# The_Flying_Jalapeno_v01.net
KiCad netlist of a schematic drawn in EAGLE
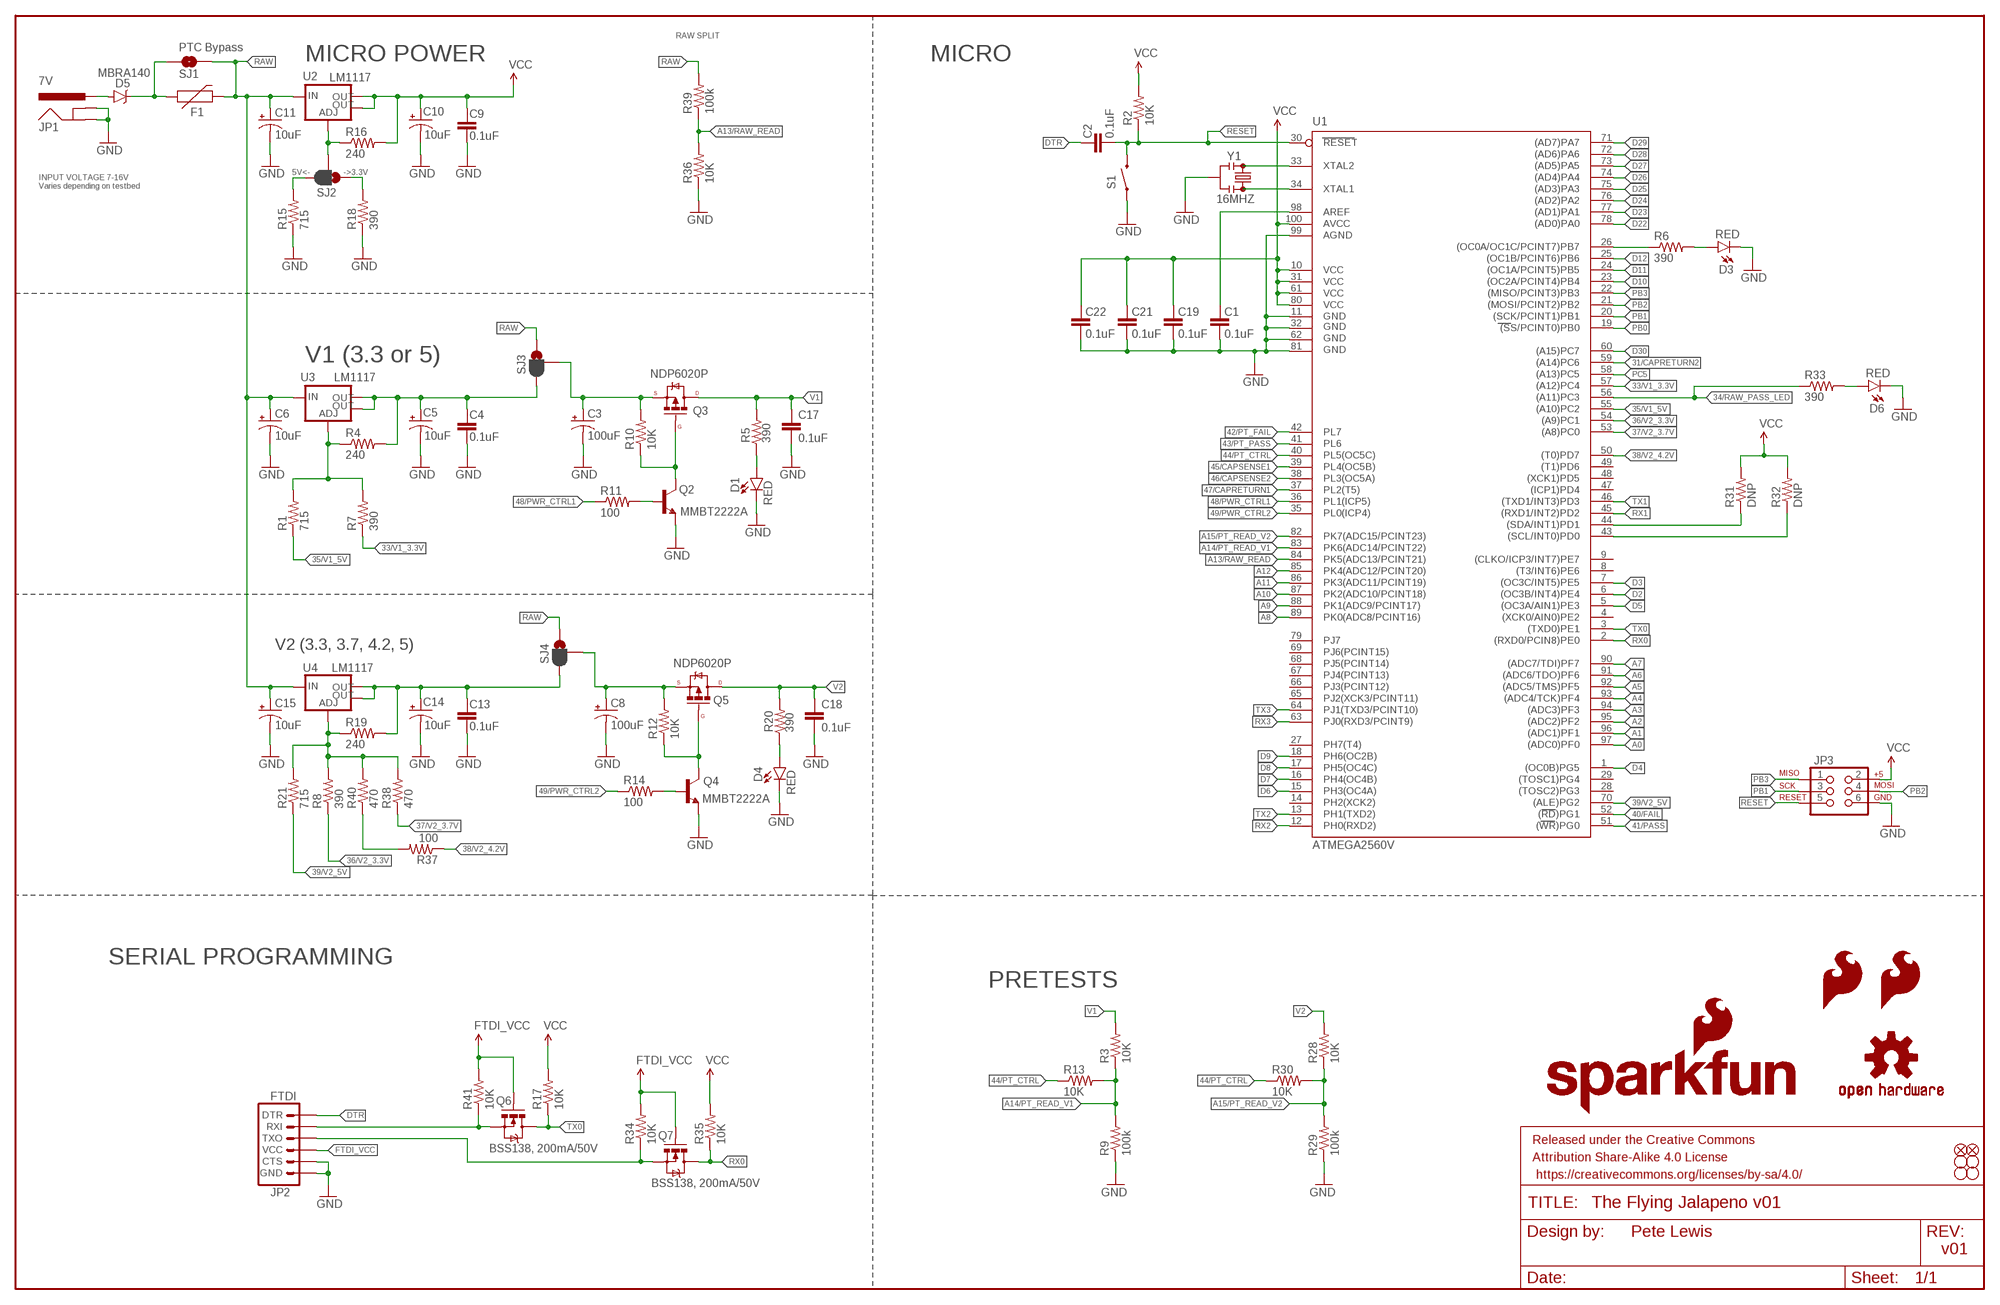
[diagram p0: schematic, sheet 1, part 1 of 2]
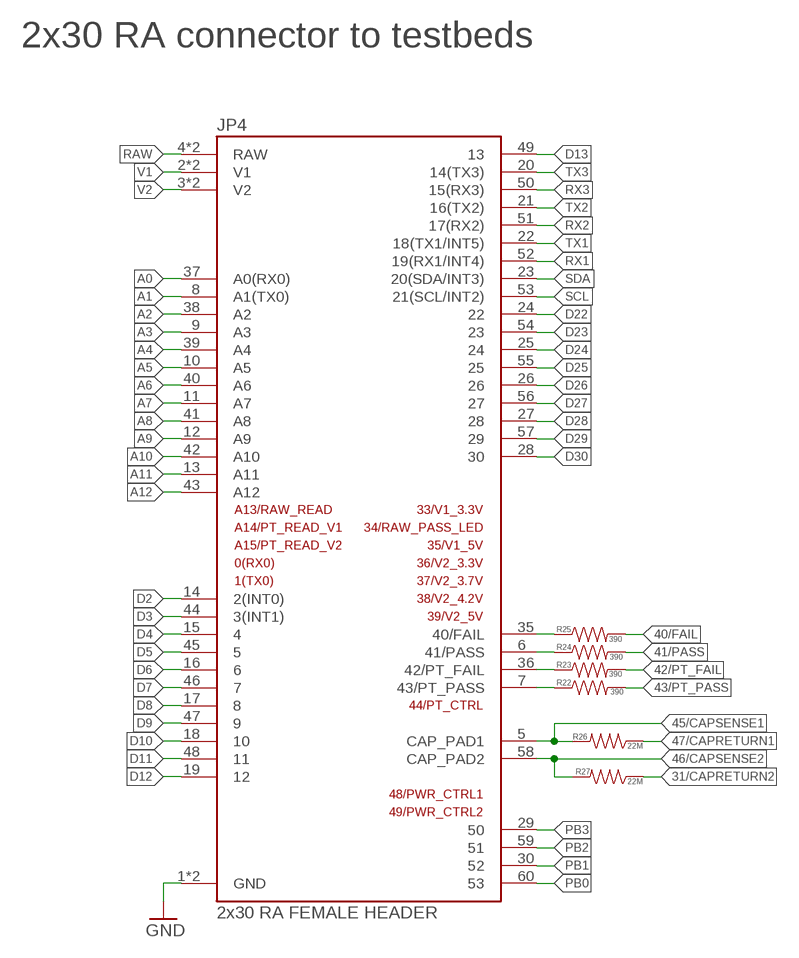
[diagram p1: schematic, sheet 1, part 2 of 2]

(export (version "E")
  (design (tool "Eeschema 10.0.6"))
  (components
    (comp (ref "C1")
      (value "0.1uF")
      (footprint "eagle-import:0603-CAP")
      (libsource (lib "eagle-import") (part "0.1UF-25V(+80/-20%)(0603)"))
    )
    (comp (ref "C2")
      (value "0.1uF")
      (footprint "eagle-import:0603-CAP")
      (libsource (lib "eagle-import") (part "0.1UF-25V(+80/-20%)(0603)"))
    )
    (comp (ref "C3")
      (value "100uF")
      (footprint "eagle-import:NIC_10X10.5_CAP")
      (libsource (lib "eagle-import") (part "100UF-63V-20%(ELECT)"))
    )
    (comp (ref "C4")
      (value "0.1uF")
      (footprint "eagle-import:0603-CAP")
      (libsource (lib "eagle-import") (part "0.1UF-25V(+80/-20%)(0603)"))
    )
    (comp (ref "C5")
      (value "10uF")
      (footprint "eagle-import:EIA3216")
      (libsource (lib "eagle-import") (part "10UF-16V-10%(TANT)"))
    )
    (comp (ref "C6")
      (value "10uF")
      (footprint "eagle-import:EIA3216")
      (libsource (lib "eagle-import") (part "10UF-16V-10%(TANT)"))
    )
    (comp (ref "C8")
      (value "100uF")
      (footprint "eagle-import:NIC_10X10.5_CAP")
      (libsource (lib "eagle-import") (part "100UF-63V-20%(ELECT)"))
    )
    (comp (ref "C9")
      (value "0.1uF")
      (footprint "eagle-import:0603-CAP")
      (libsource (lib "eagle-import") (part "0.1UF-25V(+80/-20%)(0603)"))
    )
    (comp (ref "C10")
      (value "10uF")
      (footprint "eagle-import:EIA3216")
      (libsource (lib "eagle-import") (part "10UF-16V-10%(TANT)"))
    )
    (comp (ref "C11")
      (value "10uF")
      (footprint "eagle-import:EIA3216")
      (libsource (lib "eagle-import") (part "10UF-16V-10%(TANT)"))
    )
    (comp (ref "C13")
      (value "0.1uF")
      (footprint "eagle-import:0603-CAP")
      (libsource (lib "eagle-import") (part "0.1UF-25V(+80/-20%)(0603)"))
    )
    (comp (ref "C14")
      (value "10uF")
      (footprint "eagle-import:EIA3216")
      (libsource (lib "eagle-import") (part "10UF-16V-10%(TANT)"))
    )
    (comp (ref "C15")
      (value "10uF")
      (footprint "eagle-import:EIA3216")
      (libsource (lib "eagle-import") (part "10UF-16V-10%(TANT)"))
    )
    (comp (ref "C17")
      (value "0.1uF")
      (footprint "eagle-import:0603-CAP")
      (libsource (lib "eagle-import") (part "0.1UF-25V(+80/-20%)(0603)"))
    )
    (comp (ref "C18")
      (value "0.1uF")
      (footprint "eagle-import:0603-CAP")
      (libsource (lib "eagle-import") (part "0.1UF-25V(+80/-20%)(0603)"))
    )
    (comp (ref "C19")
      (value "0.1uF")
      (footprint "eagle-import:0603-CAP")
      (libsource (lib "eagle-import") (part "0.1UF-25V(+80/-20%)(0603)"))
    )
    (comp (ref "C21")
      (value "0.1uF")
      (footprint "eagle-import:0603-CAP")
      (libsource (lib "eagle-import") (part "0.1UF-25V(+80/-20%)(0603)"))
    )
    (comp (ref "C22")
      (value "0.1uF")
      (footprint "eagle-import:0603-CAP")
      (libsource (lib "eagle-import") (part "0.1UF-25V(+80/-20%)(0603)"))
    )
    (comp (ref "D1")
      (value "RED")
      (footprint "eagle-import:LED-1206")
      (libsource (lib "eagle-import") (part "LED-RED1206"))
    )
    (comp (ref "D3")
      (value "RED")
      (footprint "eagle-import:LED-1206")
      (libsource (lib "eagle-import") (part "LED-RED1206"))
    )
    (comp (ref "D4")
      (value "RED")
      (footprint "eagle-import:LED-1206")
      (libsource (lib "eagle-import") (part "LED-RED1206"))
    )
    (comp (ref "D5")
      (value "MBRA140")
      (footprint "eagle-import:SMA-DIODE")
      (libsource (lib "eagle-import") (part "DIODE-SCHOTTKY-MBRA140"))
    )
    (comp (ref "D6")
      (value "RED")
      (footprint "eagle-import:LED-1206")
      (libsource (lib "eagle-import") (part "LED-RED1206"))
    )
    (comp (ref "F1")
      (value "PTCTHERMISTOR1206")
      (footprint "eagle-import:PTC-1206")
      (libsource (lib "eagle-import") (part "PTCTHERMISTOR1206"))
    )
    (comp (ref "FRAME1")
      (value "FRAME-LEDGER")
      (footprint "eagle-import:CREATIVE_COMMONS")
      (libsource (lib "eagle-import") (part "FRAME-LEDGER"))
    )
    (comp (ref "JP1")
      (value "7V")
      (footprint "eagle-import:POWER_JACK_PTH_LOCK")
      (libsource (lib "eagle-import") (part "POWER_JACKPTH_LOCK"))
    )
    (comp (ref "JP2")
      (value "FTDI")
      (footprint "eagle-import:1X06-SMD")
      (libsource (lib "eagle-import") (part "ARDUINO_SERIAL_PROGRAMSMD"))
    )
    (comp (ref "JP3")
      (value "AVR_SPI_PRG_6PTH")
      (footprint "eagle-import:2X3")
      (libsource (lib "eagle-import") (part "AVR_SPI_PRG_6PTH"))
    )
    (comp (ref "JP4")
      (value "2x30 RA FEMALE HEADER")
      (footprint "eagle-import:FLYING_JALAPENO_V2_F")
      (libsource (lib "eagle-import") (part "FLYING_JALAPENO_V2FEMALE"))
    )
    (comp (ref "JP5")
      (value "FIDUCIALUFIDUCIAL")
      (footprint "eagle-import:MICRO-FIDUCIAL")
      (libsource (lib "eagle-import") (part "FIDUCIALUFIDUCIAL"))
    )
    (comp (ref "JP8")
      (value "FIDUCIALUFIDUCIAL")
      (footprint "eagle-import:MICRO-FIDUCIAL")
      (libsource (lib "eagle-import") (part "FIDUCIALUFIDUCIAL"))
    )
    (comp (ref "LOGO1")
      (value "SFE_LOGO_NAME_FLAME.5_INCH")
      (footprint "eagle-import:SFE_LOGO_NAME_FLAME_.5")
      (libsource (lib "eagle-import") (part "SFE_LOGO_NAME_FLAME.5_INCH"))
    )
    (comp (ref "LOGO2")
      (value "SFE_LOGO_FLAME.3_INCH")
      (footprint "eagle-import:SFE_LOGO_FLAME_.3")
      (libsource (lib "eagle-import") (part "SFE_LOGO_FLAME.3_INCH"))
    )
    (comp (ref "LOGO3")
      (value "SFE_LOGO_FLAME.1_INCH")
      (footprint "eagle-import:SFE_LOGO_FLAME_.1")
      (libsource (lib "eagle-import") (part "SFE_LOGO_FLAME.1_INCH"))
    )
    (comp (ref "LOGO4")
      (value "OSHW-LOGOL")
      (footprint "eagle-import:OSHW-LOGO-L")
      (libsource (lib "eagle-import") (part "OSHW-LOGOL"))
    )
    (comp (ref "Q2")
      (value "MMBT2222A")
      (footprint "eagle-import:SOT23-3")
      (libsource (lib "eagle-import") (part "TRANSISTOR_NPNMMBT2222A"))
    )
    (comp (ref "Q3")
      (value "NDP6020P")
      (footprint "eagle-import:TO220V")
      (libsource (lib "eagle-import") (part "MOSFET-PCHANNELNDP6020P_20V_24A_LOW_VGS_TH"))
    )
    (comp (ref "Q4")
      (value "MMBT2222A")
      (footprint "eagle-import:SOT23-3")
      (libsource (lib "eagle-import") (part "TRANSISTOR_NPNMMBT2222A"))
    )
    (comp (ref "Q5")
      (value "NDP6020P")
      (footprint "eagle-import:TO220V")
      (libsource (lib "eagle-import") (part "MOSFET-PCHANNELNDP6020P_20V_24A_LOW_VGS_TH"))
    )
    (comp (ref "Q6")
      (value "BSS138, 200mA/50V")
      (footprint "eagle-import:SOT23-3")
      (libsource (lib "eagle-import") (part "MOSFET-NCHANNELBSS138"))
    )
    (comp (ref "Q7")
      (value "BSS138, 200mA/50V")
      (footprint "eagle-import:SOT23-3")
      (libsource (lib "eagle-import") (part "MOSFET-NCHANNELBSS138"))
    )
    (comp (ref "R1")
      (value "715")
      (footprint "eagle-import:0603-RES")
      (libsource (lib "eagle-import") (part "715OHM1/10W1%(0603)"))
    )
    (comp (ref "R2")
      (value "10K")
      (footprint "eagle-import:0603-RES")
      (libsource (lib "eagle-import") (part "10KOHM-1/10W-1%(0603)0603"))
    )
    (comp (ref "R3")
      (value "10K")
      (footprint "eagle-import:0603-RES")
      (libsource (lib "eagle-import") (part "10KOHM-1/10W-1%(0603)0603"))
    )
    (comp (ref "R4")
      (value "240")
      (footprint "eagle-import:0603-RES")
      (libsource (lib "eagle-import") (part "240OHM1/10W1%(0603)"))
    )
    (comp (ref "R5")
      (value "390")
      (footprint "eagle-import:0603-RES")
      (libsource (lib "eagle-import") (part "390OHM1/10W1%(0603)"))
    )
    (comp (ref "R6")
      (value "390")
      (footprint "eagle-import:0603-RES")
      (libsource (lib "eagle-import") (part "390OHM1/10W1%(0603)"))
    )
    (comp (ref "R7")
      (value "390")
      (footprint "eagle-import:0603-RES")
      (libsource (lib "eagle-import") (part "390OHM1/10W1%(0603)"))
    )
    (comp (ref "R8")
      (value "390")
      (footprint "eagle-import:0603-RES")
      (libsource (lib "eagle-import") (part "390OHM1/10W1%(0603)"))
    )
    (comp (ref "R9")
      (value "100k")
      (footprint "eagle-import:0603-RES")
      (libsource (lib "eagle-import") (part "100KOHM-1/10W-1%(0603)"))
    )
    (comp (ref "R10")
      (value "10K")
      (footprint "eagle-import:0603-RES")
      (libsource (lib "eagle-import") (part "10KOHM-1/10W-1%(0603)0603"))
    )
    (comp (ref "R11")
      (value "100")
      (footprint "eagle-import:0603-RES")
      (libsource (lib "eagle-import") (part "100OHM-1/10W-1%(0603)"))
    )
    (comp (ref "R12")
      (value "10K")
      (footprint "eagle-import:0603-RES")
      (libsource (lib "eagle-import") (part "10KOHM-1/10W-1%(0603)0603"))
    )
    (comp (ref "R13")
      (value "10K")
      (footprint "eagle-import:0603-RES")
      (libsource (lib "eagle-import") (part "10KOHM-1/10W-1%(0603)0603"))
    )
    (comp (ref "R14")
      (value "100")
      (footprint "eagle-import:0603-RES")
      (libsource (lib "eagle-import") (part "100OHM-1/10W-1%(0603)"))
    )
    (comp (ref "R15")
      (value "715")
      (footprint "eagle-import:0603-RES")
      (libsource (lib "eagle-import") (part "715OHM1/10W1%(0603)"))
    )
    (comp (ref "R16")
      (value "240")
      (footprint "eagle-import:0603-RES")
      (libsource (lib "eagle-import") (part "240OHM1/10W1%(0603)"))
    )
    (comp (ref "R17")
      (value "10K")
      (footprint "eagle-import:0603-RES")
      (libsource (lib "eagle-import") (part "10KOHM-1/10W-1%(0603)0603"))
    )
    (comp (ref "R18")
      (value "390")
      (footprint "eagle-import:0603-RES")
      (libsource (lib "eagle-import") (part "390OHM1/10W1%(0603)"))
    )
    (comp (ref "R19")
      (value "240")
      (footprint "eagle-import:0603-RES")
      (libsource (lib "eagle-import") (part "240OHM1/10W1%(0603)"))
    )
    (comp (ref "R20")
      (value "390")
      (footprint "eagle-import:0603-RES")
      (libsource (lib "eagle-import") (part "390OHM1/10W1%(0603)"))
    )
    (comp (ref "R21")
      (value "715")
      (footprint "eagle-import:0603-RES")
      (libsource (lib "eagle-import") (part "715OHM1/10W1%(0603)"))
    )
    (comp (ref "R22")
      (value "390")
      (footprint "eagle-import:0603-RES")
      (libsource (lib "eagle-import") (part "390OHM1/10W1%(0603)"))
    )
    (comp (ref "R23")
      (value "390")
      (footprint "eagle-import:0603-RES")
      (libsource (lib "eagle-import") (part "390OHM1/10W1%(0603)"))
    )
    (comp (ref "R24")
      (value "390")
      (footprint "eagle-import:0603-RES")
      (libsource (lib "eagle-import") (part "390OHM1/10W1%(0603)"))
    )
    (comp (ref "R25")
      (value "390")
      (footprint "eagle-import:0603-RES")
      (libsource (lib "eagle-import") (part "390OHM1/10W1%(0603)"))
    )
    (comp (ref "R26")
      (value "22M")
      (footprint "eagle-import:0603-RES")
      (libsource (lib "eagle-import") (part "22MOHM-1/10W-10%(0603)"))
    )
    (comp (ref "R27")
      (value "22M")
      (footprint "eagle-import:0603-RES")
      (libsource (lib "eagle-import") (part "22MOHM-1/10W-10%(0603)"))
    )
    (comp (ref "R28")
      (value "10K")
      (footprint "eagle-import:0603-RES")
      (libsource (lib "eagle-import") (part "10KOHM-1/10W-1%(0603)0603"))
    )
    (comp (ref "R29")
      (value "100k")
      (footprint "eagle-import:0603-RES")
      (libsource (lib "eagle-import") (part "100KOHM-1/10W-1%(0603)"))
    )
    (comp (ref "R30")
      (value "10K")
      (footprint "eagle-import:0603-RES")
      (libsource (lib "eagle-import") (part "10KOHM-1/10W-1%(0603)0603"))
    )
    (comp (ref "R31")
      (value "DNP")
      (footprint "eagle-import:0603-RES")
      (libsource (lib "eagle-import") (part "10KOHM-1/10W-1%(0603)0603"))
    )
    (comp (ref "R32")
      (value "DNP")
      (footprint "eagle-import:0603-RES")
      (libsource (lib "eagle-import") (part "10KOHM-1/10W-1%(0603)0603"))
    )
    (comp (ref "R33")
      (value "390")
      (footprint "eagle-import:0603-RES")
      (libsource (lib "eagle-import") (part "390OHM1/10W1%(0603)"))
    )
    (comp (ref "R34")
      (value "10K")
      (footprint "eagle-import:0603-RES")
      (libsource (lib "eagle-import") (part "10KOHM-1/10W-1%(0603)0603"))
    )
    (comp (ref "R35")
      (value "10K")
      (footprint "eagle-import:0603-RES")
      (libsource (lib "eagle-import") (part "10KOHM-1/10W-1%(0603)0603"))
    )
    (comp (ref "R36")
      (value "10K")
      (footprint "eagle-import:0603-RES")
      (libsource (lib "eagle-import") (part "10KOHM-1/10W-1%(0603)0603"))
    )
    (comp (ref "R37")
      (value "100")
      (footprint "eagle-import:0603-RES")
      (libsource (lib "eagle-import") (part "100OHM-1/10W-1%(0603)"))
    )
    (comp (ref "R38")
      (value "470")
      (footprint "eagle-import:0603-RES")
      (libsource (lib "eagle-import") (part "470OHM1/10W1%(0603)"))
    )
    (comp (ref "R39")
      (value "100k")
      (footprint "eagle-import:0603-RES")
      (libsource (lib "eagle-import") (part "100KOHM-1/10W-1%(0603)"))
    )
    (comp (ref "R40")
      (value "470")
      (footprint "eagle-import:0603-RES")
      (libsource (lib "eagle-import") (part "470OHM1/10W1%(0603)"))
    )
    (comp (ref "R41")
      (value "10K")
      (footprint "eagle-import:0603-RES")
      (libsource (lib "eagle-import") (part "10KOHM-1/10W-1%(0603)0603"))
    )
    (comp (ref "S1")
      (value "SWITCH-MOMENTARY-2SMD-REDUNDANT")
      (footprint "eagle-import:TACTILE-SWITCH-SMD")
      (libsource (lib "eagle-import") (part "SWITCH-MOMENTARY-2SMD-REDUNDANT"))
    )
    (comp (ref "SJ1")
      (value "PTC Bypass")
      (footprint "eagle-import:PAD-JUMPER-2-NO_NO_SILK")
      (libsource (lib "eagle-import") (part "JUMPER-PAD-2-NO"))
    )
    (comp (ref "SJ2")
      (value "JUMPER-PAD-3-2OF3_NC_BY_PASTE")
      (footprint "eagle-import:PAD-JUMPER-3-2OF3_NC_BY_PASTE_YES_SILK_FULL_BOX")
      (libsource (lib "eagle-import") (part "JUMPER-PAD-3-2OF3_NC_BY_PASTE"))
    )
    (comp (ref "SJ3")
      (value "JUMPER-PAD-3-2OF3_NC_BY_PASTE")
      (footprint "eagle-import:PAD-JUMPER-3-2OF3_NC_BY_PASTE_YES_SILK_FULL_BOX")
      (libsource (lib "eagle-import") (part "JUMPER-PAD-3-2OF3_NC_BY_PASTE"))
    )
    (comp (ref "SJ4")
      (value "JUMPER-PAD-3-2OF3_NC_BY_PASTE")
      (footprint "eagle-import:PAD-JUMPER-3-2OF3_NC_BY_PASTE_YES_SILK_FULL_BOX")
      (libsource (lib "eagle-import") (part "JUMPER-PAD-3-2OF3_NC_BY_PASTE"))
    )
    (comp (ref "STANDOFF1")
      (value "STAND-OFFTIGHT")
      (footprint "eagle-import:STAND-OFF-TIGHT")
      (libsource (lib "eagle-import") (part "STAND-OFFTIGHT"))
    )
    (comp (ref "STANDOFF2")
      (value "STAND-OFFTIGHT")
      (footprint "eagle-import:STAND-OFF-TIGHT")
      (libsource (lib "eagle-import") (part "STAND-OFFTIGHT"))
    )
    (comp (ref "STANDOFF3")
      (value "STAND-OFFTIGHT")
      (footprint "eagle-import:STAND-OFF-TIGHT")
      (libsource (lib "eagle-import") (part "STAND-OFFTIGHT"))
    )
    (comp (ref "STANDOFF4")
      (value "STAND-OFFTIGHT")
      (footprint "eagle-import:STAND-OFF-TIGHT")
      (libsource (lib "eagle-import") (part "STAND-OFFTIGHT"))
    )
    (comp (ref "U1")
      (value "ATMEGA2560AU")
      (footprint "eagle-import:TQFP100")
      (libsource (lib "eagle-import") (part "ATMEGA2560AU"))
    )
    (comp (ref "U2")
      (value "LM1117")
      (footprint "eagle-import:SOT223")
      (libsource (lib "eagle-import") (part "V_REG_LM1117SOT223"))
    )
    (comp (ref "U3")
      (value "LM1117")
      (footprint "eagle-import:SOT223")
      (libsource (lib "eagle-import") (part "V_REG_LM1117SOT223"))
    )
    (comp (ref "U4")
      (value "LM1117")
      (footprint "eagle-import:SOT223")
      (libsource (lib "eagle-import") (part "V_REG_LM1117SOT223"))
    )
    (comp (ref "Y1")
      (value "16MHZ")
      (footprint "eagle-import:RESONATOR-SMD")
      (libsource (lib "eagle-import") (part "RESONATOR16MHZ"))
    )
  )
  (nets
    (net (code "1") (name "31{slash}CAPRETURN2") (class "Default")
      (node (ref "R27") (pin "1") (pinfunction "1_1") (pintype "passive"))
      (node (ref "U1") (pin "59") (pinfunction "(A14)PC6_59") (pintype "bidirectional"))
    )
    (net (code "2") (name "33{slash}V1_3.3V") (class "Default")
      (node (ref "R7") (pin "1") (pinfunction "1_1") (pintype "passive"))
      (node (ref "U1") (pin "57") (pinfunction "(A12)PC4_57") (pintype "bidirectional"))
    )
    (net (code "3") (name "34{slash}RAW_PASS_LED") (class "Default")
      (node (ref "R33") (pin "1") (pinfunction "1_1") (pintype "passive"))
      (node (ref "U1") (pin "56") (pinfunction "(A11)PC3_56") (pintype "bidirectional"))
    )
    (net (code "4") (name "35{slash}V1_5V") (class "Default")
      (node (ref "R1") (pin "1") (pinfunction "1_1") (pintype "passive"))
      (node (ref "U1") (pin "55") (pinfunction "(A10)PC2_55") (pintype "bidirectional"))
    )
    (net (code "5") (name "36{slash}V2_3.3V") (class "Default")
      (node (ref "R8") (pin "1") (pinfunction "1_1") (pintype "passive"))
      (node (ref "U1") (pin "54") (pinfunction "(A9)PC1_54") (pintype "bidirectional"))
    )
    (net (code "6") (name "37{slash}V2_3.7V") (class "Default")
      (node (ref "R38") (pin "1") (pinfunction "1_1") (pintype "passive"))
      (node (ref "U1") (pin "53") (pinfunction "(A8)PC0_53") (pintype "bidirectional"))
    )
    (net (code "7") (name "38{slash}V2_4.2V") (class "Default")
      (node (ref "R37") (pin "1") (pinfunction "1_1") (pintype "passive"))
      (node (ref "U1") (pin "50") (pinfunction "(T0)PD7_50") (pintype "bidirectional"))
    )
    (net (code "8") (name "39{slash}V2_5V") (class "Default")
      (node (ref "R21") (pin "1") (pinfunction "1_1") (pintype "passive"))
      (node (ref "U1") (pin "70") (pinfunction "(ALE)PG2_70") (pintype "bidirectional"))
    )
    (net (code "9") (name "40{slash}FAIL") (class "Default")
      (node (ref "R25") (pin "2") (pinfunction "2_2") (pintype "passive"))
      (node (ref "U1") (pin "52") (pinfunction "(RD)PG1_52") (pintype "bidirectional"))
    )
    (net (code "10") (name "41{slash}PASS") (class "Default")
      (node (ref "R24") (pin "2") (pinfunction "2_2") (pintype "passive"))
      (node (ref "U1") (pin "51") (pinfunction "(WR)PG0_51") (pintype "bidirectional"))
    )
    (net (code "11") (name "42{slash}PT_FAIL") (class "Default")
      (node (ref "R23") (pin "2") (pinfunction "2_2") (pintype "passive"))
      (node (ref "U1") (pin "42") (pinfunction "PL7_42") (pintype "bidirectional"))
    )
    (net (code "12") (name "43{slash}PT_PASS") (class "Default")
      (node (ref "R22") (pin "2") (pinfunction "2_2") (pintype "passive"))
      (node (ref "U1") (pin "41") (pinfunction "PL6_41") (pintype "bidirectional"))
    )
    (net (code "13") (name "44{slash}PT_CTRL") (class "Default")
      (node (ref "R13") (pin "1") (pinfunction "1_1") (pintype "passive"))
      (node (ref "R30") (pin "1") (pinfunction "1_1") (pintype "passive"))
      (node (ref "U1") (pin "40") (pinfunction "PL5(OC5C)_40") (pintype "bidirectional"))
    )
    (net (code "14") (name "45{slash}CAPSENSE1") (class "Default")
      (node (ref "JP4") (pin "5") (pinfunction "CAP_PAD1_5") (pintype "bidirectional"))
      (node (ref "R26") (pin "2") (pinfunction "2_2") (pintype "passive"))
      (node (ref "U1") (pin "39") (pinfunction "PL4(OC5B)_39") (pintype "bidirectional"))
    )
    (net (code "15") (name "46{slash}CAPSENSE2") (class "Default")
      (node (ref "JP4") (pin "58") (pinfunction "CAP_PAD2_58") (pintype "bidirectional"))
      (node (ref "R27") (pin "2") (pinfunction "2_2") (pintype "passive"))
      (node (ref "U1") (pin "38") (pinfunction "PL3(OC5A)_38") (pintype "bidirectional"))
    )
    (net (code "16") (name "47{slash}CAPRETURN1") (class "Default")
      (node (ref "R26") (pin "1") (pinfunction "1_1") (pintype "passive"))
      (node (ref "U1") (pin "37") (pinfunction "PL2(T5)_37") (pintype "bidirectional"))
    )
    (net (code "17") (name "48{slash}PWR_CTRL1") (class "Default")
      (node (ref "R11") (pin "1") (pinfunction "1_1") (pintype "passive"))
      (node (ref "U1") (pin "36") (pinfunction "PL1(ICP5)_36") (pintype "bidirectional"))
    )
    (net (code "18") (name "49{slash}PWR_CTRL2") (class "Default")
      (node (ref "R14") (pin "1") (pinfunction "1_1") (pintype "passive"))
      (node (ref "U1") (pin "35") (pinfunction "PL0(ICP4)_35") (pintype "bidirectional"))
    )
    (net (code "19") (name "A0") (class "Default")
      (node (ref "JP4") (pin "37") (pinfunction "A0(RX0)_37") (pintype "bidirectional"))
      (node (ref "U1") (pin "97") (pinfunction "(ADC0)PF0_97") (pintype "bidirectional"))
    )
    (net (code "20") (name "A1") (class "Default")
      (node (ref "JP4") (pin "8") (pinfunction "A1(TX0)_8") (pintype "bidirectional"))
      (node (ref "U1") (pin "96") (pinfunction "(ADC1)PF1_96") (pintype "bidirectional"))
    )
    (net (code "21") (name "A2") (class "Default")
      (node (ref "JP4") (pin "38") (pinfunction "A2_38") (pintype "bidirectional"))
      (node (ref "U1") (pin "95") (pinfunction "(ADC2)PF2_95") (pintype "bidirectional"))
    )
    (net (code "22") (name "A3") (class "Default")
      (node (ref "JP4") (pin "9") (pinfunction "A3_9") (pintype "bidirectional"))
      (node (ref "U1") (pin "94") (pinfunction "(ADC3)PF3_94") (pintype "bidirectional"))
    )
    (net (code "23") (name "A4") (class "Default")
      (node (ref "JP4") (pin "39") (pinfunction "A4_39") (pintype "bidirectional"))
      (node (ref "U1") (pin "93") (pinfunction "(ADC4/TCK)PF4_93") (pintype "bidirectional"))
    )
    (net (code "24") (name "A5") (class "Default")
      (node (ref "JP4") (pin "10") (pinfunction "A5_10") (pintype "bidirectional"))
      (node (ref "U1") (pin "92") (pinfunction "(ADC5/TMS)PF5_92") (pintype "bidirectional"))
    )
    (net (code "25") (name "A6") (class "Default")
      (node (ref "JP4") (pin "40") (pinfunction "A6_40") (pintype "bidirectional"))
      (node (ref "U1") (pin "91") (pinfunction "(ADC6/TDO)PF6_91") (pintype "bidirectional"))
    )
    (net (code "26") (name "A7") (class "Default")
      (node (ref "JP4") (pin "11") (pinfunction "A7_11") (pintype "bidirectional"))
      (node (ref "U1") (pin "90") (pinfunction "(ADC7/TDI)PF7_90") (pintype "bidirectional"))
    )
    (net (code "27") (name "A8") (class "Default")
      (node (ref "JP4") (pin "41") (pinfunction "A8_41") (pintype "bidirectional"))
      (node (ref "U1") (pin "89") (pinfunction "PK0(ADC8/PCINT16)_89") (pintype "bidirectional"))
    )
    (net (code "28") (name "A9") (class "Default")
      (node (ref "JP4") (pin "12") (pinfunction "A9_12") (pintype "bidirectional"))
      (node (ref "U1") (pin "88") (pinfunction "PK1(ADC9/PCINT17)_88") (pintype "bidirectional"))
    )
    (net (code "29") (name "A10") (class "Default")
      (node (ref "JP4") (pin "42") (pinfunction "A10_42") (pintype "bidirectional"))
      (node (ref "U1") (pin "87") (pinfunction "PK2(ADC10/PCINT18)_87") (pintype "bidirectional"))
    )
    (net (code "30") (name "A11") (class "Default")
      (node (ref "JP4") (pin "13") (pinfunction "A11_13") (pintype "bidirectional"))
      (node (ref "U1") (pin "86") (pinfunction "PK3(ADC11/PCINT19)_86") (pintype "bidirectional"))
    )
    (net (code "31") (name "A12") (class "Default")
      (node (ref "JP4") (pin "43") (pinfunction "A12_43") (pintype "bidirectional"))
      (node (ref "U1") (pin "85") (pinfunction "PK4(ADC12/PCINT20)_85") (pintype "bidirectional"))
    )
    (net (code "32") (name "A13{slash}RAW_READ") (class "Default")
      (node (ref "R36") (pin "2") (pinfunction "2_2") (pintype "passive"))
      (node (ref "R39") (pin "1") (pinfunction "1_1") (pintype "passive"))
      (node (ref "U1") (pin "84") (pinfunction "PK5(ADC13/PCINT21)_84") (pintype "bidirectional"))
    )
    (net (code "33") (name "A14{slash}PT_READ_V1") (class "Default")
      (node (ref "R13") (pin "2") (pinfunction "2_2") (pintype "passive"))
      (node (ref "R3") (pin "1") (pinfunction "1_1") (pintype "passive"))
      (node (ref "R9") (pin "2") (pinfunction "2_2") (pintype "passive"))
      (node (ref "U1") (pin "83") (pinfunction "PK6(ADC14/PCINT22)_83") (pintype "bidirectional"))
    )
    (net (code "34") (name "A15{slash}PT_READ_V2") (class "Default")
      (node (ref "R28") (pin "1") (pinfunction "1_1") (pintype "passive"))
      (node (ref "R29") (pin "2") (pinfunction "2_2") (pintype "passive"))
      (node (ref "R30") (pin "2") (pinfunction "2_2") (pintype "passive"))
      (node (ref "U1") (pin "82") (pinfunction "PK7(ADC15/PCINT23)_82") (pintype "bidirectional"))
    )
    (net (code "35") (name "D2") (class "Default")
      (node (ref "JP4") (pin "14") (pinfunction "2(INT0)_14") (pintype "bidirectional"))
      (node (ref "U1") (pin "6") (pinfunction "(OC3B/INT4)PE4_6") (pintype "bidirectional"))
    )
    (net (code "36") (name "D3") (class "Default")
      (node (ref "JP4") (pin "44") (pinfunction "3(INT1)_44") (pintype "bidirectional"))
      (node (ref "U1") (pin "7") (pinfunction "(OC3C/INT5)PE5_7") (pintype "bidirectional"))
    )
    (net (code "37") (name "D4") (class "Default")
      (node (ref "JP4") (pin "15") (pinfunction "4_15") (pintype "bidirectional"))
      (node (ref "U1") (pin "1") (pinfunction "(OC0B)PG5_1") (pintype "bidirectional"))
    )
    (net (code "38") (name "D5") (class "Default")
      (node (ref "JP4") (pin "45") (pinfunction "5_45") (pintype "bidirectional"))
      (node (ref "U1") (pin "5") (pinfunction "(OC3A/AIN1)PE3_5") (pintype "bidirectional"))
    )
    (net (code "39") (name "D6") (class "Default")
      (node (ref "JP4") (pin "16") (pinfunction "6_16") (pintype "bidirectional"))
      (node (ref "U1") (pin "15") (pinfunction "PH3(OC4A)_15") (pintype "bidirectional"))
    )
    (net (code "40") (name "D7") (class "Default")
      (node (ref "JP4") (pin "46") (pinfunction "7_46") (pintype "bidirectional"))
      (node (ref "U1") (pin "16") (pinfunction "PH4(OC4B)_16") (pintype "bidirectional"))
    )
    (net (code "41") (name "D8") (class "Default")
      (node (ref "JP4") (pin "17") (pinfunction "8_17") (pintype "bidirectional"))
      (node (ref "U1") (pin "17") (pinfunction "PH5(OC4C)_17") (pintype "bidirectional"))
    )
    (net (code "42") (name "D9") (class "Default")
      (node (ref "JP4") (pin "47") (pinfunction "9_47") (pintype "bidirectional"))
      (node (ref "U1") (pin "18") (pinfunction "PH6(OC2B)_18") (pintype "bidirectional"))
    )
    (net (code "43") (name "D10") (class "Default")
      (node (ref "JP4") (pin "18") (pinfunction "10_18") (pintype "bidirectional"))
      (node (ref "U1") (pin "23") (pinfunction "(OC2A/PCINT4)PB4_23") (pintype "bidirectional"))
    )
    (net (code "44") (name "D11") (class "Default")
      (node (ref "JP4") (pin "48") (pinfunction "11_48") (pintype "bidirectional"))
      (node (ref "U1") (pin "24") (pinfunction "(OC1A/PCINT5)PB5_24") (pintype "bidirectional"))
    )
    (net (code "45") (name "D12") (class "Default")
      (node (ref "JP4") (pin "19") (pinfunction "12_19") (pintype "bidirectional"))
      (node (ref "U1") (pin "25") (pinfunction "(OC1B/PCINT6)PB6_25") (pintype "bidirectional"))
    )
    (net (code "46") (name "D13") (class "Default")
      (node (ref "JP4") (pin "49") (pinfunction "13_49") (pintype "bidirectional"))
      (node (ref "R6") (pin "1") (pinfunction "1_1") (pintype "passive"))
      (node (ref "U1") (pin "26") (pinfunction "(OC0A/OC1C/PCINT7)PB7_26") (pintype "bidirectional"))
    )
    (net (code "47") (name "D22") (class "Default")
      (node (ref "JP4") (pin "24") (pinfunction "22_24") (pintype "bidirectional"))
      (node (ref "U1") (pin "78") (pinfunction "(AD0)PA0_78") (pintype "bidirectional"))
    )
    (net (code "48") (name "D23") (class "Default")
      (node (ref "JP4") (pin "54") (pinfunction "23_54") (pintype "bidirectional"))
      (node (ref "U1") (pin "77") (pinfunction "(AD1)PA1_77") (pintype "bidirectional"))
    )
    (net (code "49") (name "D24") (class "Default")
      (node (ref "JP4") (pin "25") (pinfunction "24_25") (pintype "bidirectional"))
      (node (ref "U1") (pin "76") (pinfunction "(AD2)PA2_76") (pintype "bidirectional"))
    )
    (net (code "50") (name "D25") (class "Default")
      (node (ref "JP4") (pin "55") (pinfunction "25_55") (pintype "bidirectional"))
      (node (ref "U1") (pin "75") (pinfunction "(AD3)PA3_75") (pintype "bidirectional"))
    )
    (net (code "51") (name "D26") (class "Default")
      (node (ref "JP4") (pin "26") (pinfunction "26_26") (pintype "bidirectional"))
      (node (ref "U1") (pin "74") (pinfunction "(AD4)PA4_74") (pintype "bidirectional"))
    )
    (net (code "52") (name "D27") (class "Default")
      (node (ref "JP4") (pin "56") (pinfunction "27_56") (pintype "bidirectional"))
      (node (ref "U1") (pin "73") (pinfunction "(AD5)PA5_73") (pintype "bidirectional"))
    )
    (net (code "53") (name "D28") (class "Default")
      (node (ref "JP4") (pin "27") (pinfunction "28_27") (pintype "bidirectional"))
      (node (ref "U1") (pin "72") (pinfunction "(AD6)PA6_72") (pintype "bidirectional"))
    )
    (net (code "54") (name "D29") (class "Default")
      (node (ref "JP4") (pin "57") (pinfunction "29_57") (pintype "bidirectional"))
      (node (ref "U1") (pin "71") (pinfunction "(AD7)PA7_71") (pintype "bidirectional"))
    )
    (net (code "55") (name "D30") (class "Default")
      (node (ref "JP4") (pin "28") (pinfunction "30_28") (pintype "bidirectional"))
      (node (ref "U1") (pin "60") (pinfunction "(A15)PC7_60") (pintype "bidirectional"))
    )
    (net (code "56") (name "DTR") (class "Default")
      (node (ref "C2") (pin "2") (pinfunction "2_2") (pintype "passive"))
      (node (ref "JP2") (pin "1") (pinfunction "DTR_1") (pintype "passive"))
    )
    (net (code "57") (name "FTDI_VCC") (class "Default")
      (node (ref "JP2") (pin "4") (pinfunction "VCC_4") (pintype "passive"))
      (node (ref "Q6") (pin "1") (pinfunction "G_1") (pintype "passive"))
      (node (ref "Q7") (pin "1") (pinfunction "G_1") (pintype "passive"))
      (node (ref "R34") (pin "2") (pinfunction "2_2") (pintype "passive"))
      (node (ref "R41") (pin "2") (pinfunction "2_2") (pintype "passive"))
    )
    (net (code "58") (name "GND") (class "Default")
      (node (ref "C1") (pin "1") (pinfunction "1_1") (pintype "passive"))
      (node (ref "C10") (pin "C") (pinfunction "-_C") (pintype "passive"))
      (node (ref "C11") (pin "C") (pinfunction "-_C") (pintype "passive"))
      (node (ref "C13") (pin "2") (pinfunction "2_2") (pintype "passive"))
      (node (ref "C14") (pin "C") (pinfunction "-_C") (pintype "passive"))
      (node (ref "C15") (pin "C") (pinfunction "-_C") (pintype "passive"))
      (node (ref "C17") (pin "2") (pinfunction "2_2") (pintype "passive"))
      (node (ref "C18") (pin "2") (pinfunction "2_2") (pintype "passive"))
      (node (ref "C19") (pin "1") (pinfunction "1_1") (pintype "passive"))
      (node (ref "C21") (pin "1") (pinfunction "1_1") (pintype "passive"))
      (node (ref "C22") (pin "1") (pinfunction "1_1") (pintype "passive"))
      (node (ref "C3") (pin "-") (pinfunction "-_-") (pintype "passive"))
      (node (ref "C4") (pin "2") (pinfunction "2_2") (pintype "passive"))
      (node (ref "C5") (pin "C") (pinfunction "-_C") (pintype "passive"))
      (node (ref "C6") (pin "C") (pinfunction "-_C") (pintype "passive"))
      (node (ref "C8") (pin "-") (pinfunction "-_-") (pintype "passive"))
      (node (ref "C9") (pin "2") (pinfunction "2_2") (pintype "passive"))
      (node (ref "D1") (pin "C") (pinfunction "C_C") (pintype "passive"))
      (node (ref "D3") (pin "C") (pinfunction "C_C") (pintype "passive"))
      (node (ref "D4") (pin "C") (pinfunction "C_C") (pintype "passive"))
      (node (ref "D6") (pin "C") (pinfunction "C_C") (pintype "passive"))
      (node (ref "JP1") (pin "GND") (pinfunction "GND_GND") (pintype "bidirectional"))
      (node (ref "JP1") (pin "GNDBREAK") (pinfunction "GNDBREAK_GNDBREAK") (pintype "bidirectional"))
      (node (ref "JP2") (pin "5") (pinfunction "CTS_5") (pintype "passive"))
      (node (ref "JP2") (pin "6") (pinfunction "GND_6") (pintype "passive"))
      (node (ref "JP3") (pin "6") (pinfunction "6_6") (pintype "passive"))
      (node (ref "JP4") (pin "1") (pinfunction "GND_1") (pintype "bidirectional"))
      (node (ref "JP4") (pin "31") (pinfunction "GND_31") (pintype "bidirectional"))
      (node (ref "Q2") (pin "2") (pinfunction "E_2") (pintype "passive"))
      (node (ref "Q4") (pin "2") (pinfunction "E_2") (pintype "passive"))
      (node (ref "R15") (pin "1") (pinfunction "1_1") (pintype "passive"))
      (node (ref "R18") (pin "1") (pinfunction "1_1") (pintype "passive"))
      (node (ref "R29") (pin "1") (pinfunction "1_1") (pintype "passive"))
      (node (ref "R36") (pin "1") (pinfunction "1_1") (pintype "passive"))
      (node (ref "R9") (pin "1") (pinfunction "1_1") (pintype "passive"))
      (node (ref "S1") (pin "1") (pinfunction "1_1") (pintype "passive"))
      (node (ref "S1") (pin "2") (pinfunction "1_2") (pintype "passive"))
      (node (ref "U1") (pin "11") (pinfunction "GND_11") (pintype "power_in"))
      (node (ref "U1") (pin "32") (pinfunction "GND1_32") (pintype "power_in"))
      (node (ref "U1") (pin "62") (pinfunction "GND2_62") (pintype "power_in"))
      (node (ref "U1") (pin "81") (pinfunction "GND3_81") (pintype "power_in"))
      (node (ref "U1") (pin "99") (pinfunction "AGND_99") (pintype "power_in"))
      (node (ref "Y1") (pin "2") (pinfunction "2_2") (pintype "passive"))
    )
    (net (code "59") (name "Net-(C5-+)") (class "Default")
      (node (ref "C4") (pin "1") (pinfunction "1_1") (pintype "passive"))
      (node (ref "C5") (pin "A") (pinfunction "+_A") (pintype "passive"))
      (node (ref "R4") (pin "2") (pinfunction "2_2") (pintype "passive"))
      (node (ref "SJ3") (pin "3") (pinfunction "3_3") (pintype "passive"))
      (node (ref "U3") (pin "2") (pinfunction "OUT_2") (pintype "output"))
      (node (ref "U3") (pin "4") (pinfunction "OUT_4") (pintype "output"))
    )
    (net (code "60") (name "Net-(C14-+)") (class "Default")
      (node (ref "C13") (pin "1") (pinfunction "1_1") (pintype "passive"))
      (node (ref "C14") (pin "A") (pinfunction "+_A") (pintype "passive"))
      (node (ref "R19") (pin "2") (pinfunction "2_2") (pintype "passive"))
      (node (ref "SJ4") (pin "3") (pinfunction "3_3") (pintype "passive"))
      (node (ref "U4") (pin "2") (pinfunction "OUT_2") (pintype "output"))
      (node (ref "U4") (pin "4") (pinfunction "OUT_4") (pintype "output"))
    )
    (net (code "61") (name "Net-(D1-PadA)") (class "Default")
      (node (ref "D1") (pin "A") (pinfunction "A_A") (pintype "passive"))
      (node (ref "R5") (pin "1") (pinfunction "1_1") (pintype "passive"))
    )
    (net (code "62") (name "Net-(D3-PadA)") (class "Default")
      (node (ref "D3") (pin "A") (pinfunction "A_A") (pintype "passive"))
      (node (ref "R6") (pin "2") (pinfunction "2_2") (pintype "passive"))
    )
    (net (code "63") (name "Net-(D4-PadA)") (class "Default")
      (node (ref "D4") (pin "A") (pinfunction "A_A") (pintype "passive"))
      (node (ref "R20") (pin "1") (pinfunction "1_1") (pintype "passive"))
    )
    (net (code "64") (name "Net-(D5-PadA)") (class "Default")
      (node (ref "D5") (pin "A") (pinfunction "A_A") (pintype "passive"))
      (node (ref "JP1") (pin "PWR") (pinfunction "PWR_PWR") (pintype "bidirectional"))
    )
    (net (code "65") (name "Net-(D5-PadC)") (class "Default")
      (node (ref "D5") (pin "C") (pinfunction "C_C") (pintype "passive"))
      (node (ref "F1") (pin "1") (pinfunction "1_1") (pintype "bidirectional"))
      (node (ref "SJ1") (pin "1") (pinfunction "1_1") (pintype "passive"))
    )
    (net (code "66") (name "Net-(D6-PadA)") (class "Default")
      (node (ref "D6") (pin "A") (pinfunction "A_A") (pintype "passive"))
      (node (ref "R33") (pin "2") (pinfunction "2_2") (pintype "passive"))
    )
    (net (code "67") (name "Net-(JP2-RXI)") (class "Default")
      (node (ref "JP2") (pin "2") (pinfunction "RXI_2") (pintype "passive"))
      (node (ref "Q6") (pin "2") (pinfunction "S_2") (pintype "passive"))
      (node (ref "R41") (pin "1") (pinfunction "1_1") (pintype "passive"))
    )
    (net (code "68") (name "Net-(JP2-TXO)") (class "Default")
      (node (ref "JP2") (pin "3") (pinfunction "TXO_3") (pintype "passive"))
      (node (ref "Q7") (pin "2") (pinfunction "S_2") (pintype "passive"))
      (node (ref "R34") (pin "1") (pinfunction "1_1") (pintype "passive"))
    )
    (net (code "69") (name "Net-(JP4-40{slash}FAIL)") (class "Default")
      (node (ref "JP4") (pin "35") (pinfunction "40/FAIL_35") (pintype "bidirectional"))
      (node (ref "R25") (pin "1") (pinfunction "1_1") (pintype "passive"))
    )
    (net (code "70") (name "Net-(JP4-41{slash}PASS)") (class "Default")
      (node (ref "JP4") (pin "6") (pinfunction "41/PASS_6") (pintype "bidirectional"))
      (node (ref "R24") (pin "1") (pinfunction "1_1") (pintype "passive"))
    )
    (net (code "71") (name "Net-(JP4-42{slash}PT_FAIL)") (class "Default")
      (node (ref "JP4") (pin "36") (pinfunction "42/PT_FAIL_36") (pintype "bidirectional"))
      (node (ref "R23") (pin "1") (pinfunction "1_1") (pintype "passive"))
    )
    (net (code "72") (name "Net-(JP4-43{slash}PT_PASS)") (class "Default")
      (node (ref "JP4") (pin "7") (pinfunction "43/PT_PASS_7") (pintype "bidirectional"))
      (node (ref "R22") (pin "1") (pinfunction "1_1") (pintype "passive"))
    )
    (net (code "73") (name "Net-(Q2-B)") (class "Default")
      (node (ref "Q2") (pin "1") (pinfunction "B_1") (pintype "passive"))
      (node (ref "R11") (pin "2") (pinfunction "2_2") (pintype "passive"))
    )
    (net (code "74") (name "Net-(Q2-C)") (class "Default")
      (node (ref "Q2") (pin "3") (pinfunction "C_3") (pintype "passive"))
      (node (ref "Q3") (pin "1") (pinfunction "G_1") (pintype "passive"))
      (node (ref "R10") (pin "1") (pinfunction "1_1") (pintype "passive"))
    )
    (net (code "75") (name "Net-(Q3-S)") (class "Default")
      (node (ref "C3") (pin "+") (pinfunction "+_+") (pintype "passive"))
      (node (ref "Q3") (pin "3") (pinfunction "S_3") (pintype "passive"))
      (node (ref "R10") (pin "2") (pinfunction "2_2") (pintype "passive"))
      (node (ref "SJ3") (pin "2") (pinfunction "2_2") (pintype "passive"))
    )
    (net (code "76") (name "Net-(Q4-B)") (class "Default")
      (node (ref "Q4") (pin "1") (pinfunction "B_1") (pintype "passive"))
      (node (ref "R14") (pin "2") (pinfunction "2_2") (pintype "passive"))
    )
    (net (code "77") (name "Net-(Q4-C)") (class "Default")
      (node (ref "Q4") (pin "3") (pinfunction "C_3") (pintype "passive"))
      (node (ref "Q5") (pin "1") (pinfunction "G_1") (pintype "passive"))
      (node (ref "R12") (pin "1") (pinfunction "1_1") (pintype "passive"))
    )
    (net (code "78") (name "Net-(Q5-S)") (class "Default")
      (node (ref "C8") (pin "+") (pinfunction "+_+") (pintype "passive"))
      (node (ref "Q5") (pin "3") (pinfunction "S_3") (pintype "passive"))
      (node (ref "R12") (pin "2") (pinfunction "2_2") (pintype "passive"))
      (node (ref "SJ4") (pin "2") (pinfunction "2_2") (pintype "passive"))
    )
    (net (code "79") (name "Net-(R15-Pad2)") (class "Default")
      (node (ref "R15") (pin "2") (pinfunction "2_2") (pintype "passive"))
      (node (ref "SJ2") (pin "3") (pinfunction "3_3") (pintype "passive"))
    )
    (net (code "80") (name "Net-(R18-Pad2)") (class "Default")
      (node (ref "R18") (pin "2") (pinfunction "2_2") (pintype "passive"))
      (node (ref "SJ2") (pin "1") (pinfunction "1_1") (pintype "passive"))
    )
    (net (code "81") (name "Net-(R37-Pad2)") (class "Default")
      (node (ref "R37") (pin "2") (pinfunction "2_2") (pintype "passive"))
      (node (ref "R40") (pin "1") (pinfunction "1_1") (pintype "passive"))
    )
    (net (code "82") (name "Net-(U1-AREF)") (class "Default")
      (node (ref "C1") (pin "2") (pinfunction "2_2") (pintype "passive"))
      (node (ref "U1") (pin "98") (pinfunction "AREF_98") (pintype "bidirectional"))
    )
    (net (code "83") (name "Net-(U1-XTAL1)") (class "Default")
      (node (ref "U1") (pin "34") (pinfunction "XTAL1_34") (pintype "input"))
      (node (ref "Y1") (pin "1") (pinfunction "1_1") (pintype "passive"))
    )
    (net (code "84") (name "Net-(U1-XTAL2)") (class "Default")
      (node (ref "U1") (pin "33") (pinfunction "XTAL2_33") (pintype "output"))
      (node (ref "Y1") (pin "3") (pinfunction "3_3") (pintype "passive"))
    )
    (net (code "85") (name "Net-(U2-ADJ)") (class "Default")
      (node (ref "R16") (pin "1") (pinfunction "1_1") (pintype "passive"))
      (node (ref "SJ2") (pin "2") (pinfunction "2_2") (pintype "passive"))
      (node (ref "U2") (pin "1") (pinfunction "ADJ_1") (pintype "input"))
    )
    (net (code "86") (name "Net-(U3-ADJ)") (class "Default")
      (node (ref "R1") (pin "2") (pinfunction "2_2") (pintype "passive"))
      (node (ref "R4") (pin "1") (pinfunction "1_1") (pintype "passive"))
      (node (ref "R7") (pin "2") (pinfunction "2_2") (pintype "passive"))
      (node (ref "U3") (pin "1") (pinfunction "ADJ_1") (pintype "input"))
    )
    (net (code "87") (name "Net-(U4-ADJ)") (class "Default")
      (node (ref "R19") (pin "1") (pinfunction "1_1") (pintype "passive"))
      (node (ref "R21") (pin "2") (pinfunction "2_2") (pintype "passive"))
      (node (ref "R38") (pin "2") (pinfunction "2_2") (pintype "passive"))
      (node (ref "R40") (pin "2") (pinfunction "2_2") (pintype "passive"))
      (node (ref "R8") (pin "2") (pinfunction "2_2") (pintype "passive"))
      (node (ref "U4") (pin "1") (pinfunction "ADJ_1") (pintype "input"))
    )
    (net (code "88") (name "PB0") (class "Default")
      (node (ref "JP4") (pin "60") (pinfunction "53_60") (pintype "bidirectional"))
      (node (ref "U1") (pin "19") (pinfunction "(SS/PCINT0)PB0_19") (pintype "bidirectional"))
    )
    (net (code "89") (name "PB1") (class "Default")
      (node (ref "JP3") (pin "3") (pinfunction "3_3") (pintype "passive"))
      (node (ref "JP4") (pin "30") (pinfunction "52_30") (pintype "bidirectional"))
      (node (ref "U1") (pin "20") (pinfunction "(SCK/PCINT1)PB1_20") (pintype "bidirectional"))
    )
    (net (code "90") (name "PB2") (class "Default")
      (node (ref "JP3") (pin "4") (pinfunction "4_4") (pintype "passive"))
      (node (ref "JP4") (pin "59") (pinfunction "51_59") (pintype "bidirectional"))
      (node (ref "U1") (pin "21") (pinfunction "(MOSI/PCINT2)PB2_21") (pintype "bidirectional"))
    )
    (net (code "91") (name "PB3") (class "Default")
      (node (ref "JP3") (pin "1") (pinfunction "1_1") (pintype "passive"))
      (node (ref "JP4") (pin "29") (pinfunction "50_29") (pintype "bidirectional"))
      (node (ref "U1") (pin "22") (pinfunction "(MISO/PCINT3)PB3_22") (pintype "bidirectional"))
    )
    (net (code "92") (name "PC5") (class "Default")
      (node (ref "U1") (pin "58") (pinfunction "(A13)PC5_58") (pintype "bidirectional"))
    )
    (net (code "93") (name "RAW") (class "Default")
      (node (ref "C11") (pin "A") (pinfunction "+_A") (pintype "passive"))
      (node (ref "C15") (pin "A") (pinfunction "+_A") (pintype "passive"))
      (node (ref "C6") (pin "A") (pinfunction "+_A") (pintype "passive"))
      (node (ref "F1") (pin "2") (pinfunction "2_2") (pintype "bidirectional"))
      (node (ref "JP4") (pin "34") (pinfunction "RAW_34") (pintype "bidirectional"))
      (node (ref "JP4") (pin "4") (pinfunction "RAW_4") (pintype "bidirectional"))
      (node (ref "R39") (pin "2") (pinfunction "2_2") (pintype "passive"))
      (node (ref "SJ1") (pin "2") (pinfunction "2_2") (pintype "passive"))
      (node (ref "SJ3") (pin "1") (pinfunction "1_1") (pintype "passive"))
      (node (ref "SJ4") (pin "1") (pinfunction "1_1") (pintype "passive"))
      (node (ref "U2") (pin "3") (pinfunction "IN_3") (pintype "input"))
      (node (ref "U3") (pin "3") (pinfunction "IN_3") (pintype "input"))
      (node (ref "U4") (pin "3") (pinfunction "IN_3") (pintype "input"))
    )
    (net (code "94") (name "RESET") (class "Default")
      (node (ref "C2") (pin "1") (pinfunction "1_1") (pintype "passive"))
      (node (ref "JP3") (pin "5") (pinfunction "5_5") (pintype "passive"))
      (node (ref "R2") (pin "1") (pinfunction "1_1") (pintype "passive"))
      (node (ref "S1") (pin "3") (pinfunction "2_3") (pintype "passive"))
      (node (ref "S1") (pin "4") (pinfunction "2_4") (pintype "passive"))
      (node (ref "U1") (pin "30") (pinfunction "RESET_30") (pintype "input"))
    )
    (net (code "95") (name "RX0") (class "Default")
      (node (ref "Q7") (pin "3") (pinfunction "D_3") (pintype "passive"))
      (node (ref "R35") (pin "1") (pinfunction "1_1") (pintype "passive"))
      (node (ref "U1") (pin "2") (pinfunction "(RXD0/PCIN8)PE0_2") (pintype "bidirectional"))
    )
    (net (code "96") (name "RX1") (class "Default")
      (node (ref "JP4") (pin "52") (pinfunction "19(RX1/INT4)_52") (pintype "bidirectional"))
      (node (ref "U1") (pin "45") (pinfunction "(RXD1/INT2)PD2_45") (pintype "bidirectional"))
    )
    (net (code "97") (name "RX2") (class "Default")
      (node (ref "JP4") (pin "51") (pinfunction "17(RX2)_51") (pintype "bidirectional"))
      (node (ref "U1") (pin "12") (pinfunction "PH0(RXD2)_12") (pintype "bidirectional"))
    )
    (net (code "98") (name "RX3") (class "Default")
      (node (ref "JP4") (pin "50") (pinfunction "15(RX3)_50") (pintype "bidirectional"))
      (node (ref "U1") (pin "63") (pinfunction "PJ0(RXD3/PCINT9)_63") (pintype "bidirectional"))
    )
    (net (code "99") (name "SCL") (class "Default")
      (node (ref "JP4") (pin "53") (pinfunction "21(SCL/INT2)_53") (pintype "bidirectional"))
      (node (ref "R32") (pin "1") (pinfunction "1_1") (pintype "passive"))
      (node (ref "U1") (pin "43") (pinfunction "(SCL/INT0)PD0_43") (pintype "bidirectional"))
    )
    (net (code "100") (name "SDA") (class "Default")
      (node (ref "JP4") (pin "23") (pinfunction "20(SDA/INT3)_23") (pintype "bidirectional"))
      (node (ref "R31") (pin "1") (pinfunction "1_1") (pintype "passive"))
      (node (ref "U1") (pin "44") (pinfunction "(SDA/INT1)PD1_44") (pintype "bidirectional"))
    )
    (net (code "101") (name "TX0") (class "Default")
      (node (ref "Q6") (pin "3") (pinfunction "D_3") (pintype "passive"))
      (node (ref "R17") (pin "1") (pinfunction "1_1") (pintype "passive"))
      (node (ref "U1") (pin "3") (pinfunction "(TXD0)PE1_3") (pintype "bidirectional"))
    )
    (net (code "102") (name "TX1") (class "Default")
      (node (ref "JP4") (pin "22") (pinfunction "18(TX1/INT5)_22") (pintype "bidirectional"))
      (node (ref "U1") (pin "46") (pinfunction "(TXD1/INT3)PD3_46") (pintype "bidirectional"))
    )
    (net (code "103") (name "TX2") (class "Default")
      (node (ref "JP4") (pin "21") (pinfunction "16(TX2)_21") (pintype "bidirectional"))
      (node (ref "U1") (pin "13") (pinfunction "PH1(TXD2)_13") (pintype "bidirectional"))
    )
    (net (code "104") (name "TX3") (class "Default")
      (node (ref "JP4") (pin "20") (pinfunction "14(TX3)_20") (pintype "bidirectional"))
      (node (ref "U1") (pin "64") (pinfunction "PJ1(TXD3/PCINT10)_64") (pintype "bidirectional"))
    )
    (net (code "105") (name "V1") (class "Default")
      (node (ref "C17") (pin "1") (pinfunction "1_1") (pintype "passive"))
      (node (ref "JP4") (pin "2") (pinfunction "V1_2") (pintype "bidirectional"))
      (node (ref "JP4") (pin "32") (pinfunction "V1_32") (pintype "bidirectional"))
      (node (ref "Q3") (pin "2") (pinfunction "D_2") (pintype "passive"))
      (node (ref "R3") (pin "2") (pinfunction "2_2") (pintype "passive"))
      (node (ref "R5") (pin "2") (pinfunction "2_2") (pintype "passive"))
    )
    (net (code "106") (name "V2") (class "Default")
      (node (ref "C18") (pin "1") (pinfunction "1_1") (pintype "passive"))
      (node (ref "JP4") (pin "3") (pinfunction "V2_3") (pintype "bidirectional"))
      (node (ref "JP4") (pin "33") (pinfunction "V2_33") (pintype "bidirectional"))
      (node (ref "Q5") (pin "2") (pinfunction "D_2") (pintype "passive"))
      (node (ref "R20") (pin "2") (pinfunction "2_2") (pintype "passive"))
      (node (ref "R28") (pin "2") (pinfunction "2_2") (pintype "passive"))
    )
    (net (code "107") (name "VCC") (class "Default")
      (node (ref "C10") (pin "A") (pinfunction "+_A") (pintype "passive"))
      (node (ref "C19") (pin "2") (pinfunction "2_2") (pintype "passive"))
      (node (ref "C21") (pin "2") (pinfunction "2_2") (pintype "passive"))
      (node (ref "C22") (pin "2") (pinfunction "2_2") (pintype "passive"))
      (node (ref "C9") (pin "1") (pinfunction "1_1") (pintype "passive"))
      (node (ref "JP3") (pin "2") (pinfunction "2_2") (pintype "passive"))
      (node (ref "R16") (pin "2") (pinfunction "2_2") (pintype "passive"))
      (node (ref "R17") (pin "2") (pinfunction "2_2") (pintype "passive"))
      (node (ref "R2") (pin "2") (pinfunction "2_2") (pintype "passive"))
      (node (ref "R31") (pin "2") (pinfunction "2_2") (pintype "passive"))
      (node (ref "R32") (pin "2") (pinfunction "2_2") (pintype "passive"))
      (node (ref "R35") (pin "2") (pinfunction "2_2") (pintype "passive"))
      (node (ref "U1") (pin "10") (pinfunction "VCC_10") (pintype "power_in"))
      (node (ref "U1") (pin "100") (pinfunction "AVCC_100") (pintype "power_in"))
      (node (ref "U1") (pin "31") (pinfunction "VCC1_31") (pintype "power_in"))
      (node (ref "U1") (pin "61") (pinfunction "VCC2_61") (pintype "power_in"))
      (node (ref "U1") (pin "80") (pinfunction "VCC3_80") (pintype "power_in"))
      (node (ref "U2") (pin "2") (pinfunction "OUT_2") (pintype "output"))
      (node (ref "U2") (pin "4") (pinfunction "OUT_4") (pintype "output"))
    )
    (net (code "108") (name "unconnected-(U1-(CLKO{slash}ICP3{slash}INT7)PE7-Pad9)") (class "Default")
      (node (ref "U1") (pin "9") (pinfunction "(CLKO/ICP3/INT7)PE7_9") (pintype "bidirectional"))
    )
    (net (code "109") (name "unconnected-(U1-(ICP1)PD4-Pad47)") (class "Default")
      (node (ref "U1") (pin "47") (pinfunction "(ICP1)PD4_47") (pintype "bidirectional"))
    )
    (net (code "110") (name "unconnected-(U1-(T1)PD6-Pad49)") (class "Default")
      (node (ref "U1") (pin "49") (pinfunction "(T1)PD6_49") (pintype "bidirectional"))
    )
    (net (code "111") (name "unconnected-(U1-(T3{slash}INT6)PE6-Pad8)") (class "Default")
      (node (ref "U1") (pin "8") (pinfunction "(T3/INT6)PE6_8") (pintype "bidirectional"))
    )
    (net (code "112") (name "unconnected-(U1-(TOSC1)PG4-Pad29)") (class "Default")
      (node (ref "U1") (pin "29") (pinfunction "(TOSC1)PG4_29") (pintype "bidirectional"))
    )
    (net (code "113") (name "unconnected-(U1-(TOSC2)PG3-Pad28)") (class "Default")
      (node (ref "U1") (pin "28") (pinfunction "(TOSC2)PG3_28") (pintype "bidirectional"))
    )
    (net (code "114") (name "unconnected-(U1-(XCK0{slash}AIN0)PE2-Pad4)") (class "Default")
      (node (ref "U1") (pin "4") (pinfunction "(XCK0/AIN0)PE2_4") (pintype "bidirectional"))
    )
    (net (code "115") (name "unconnected-(U1-(XCK1)PD5-Pad48)") (class "Default")
      (node (ref "U1") (pin "48") (pinfunction "(XCK1)PD5_48") (pintype "bidirectional"))
    )
    (net (code "116") (name "unconnected-(U1-PH2(XCK2)-Pad14)") (class "Default")
      (node (ref "U1") (pin "14") (pinfunction "PH2(XCK2)_14") (pintype "bidirectional"))
    )
    (net (code "117") (name "unconnected-(U1-PH7(T4)-Pad27)") (class "Default")
      (node (ref "U1") (pin "27") (pinfunction "PH7(T4)_27") (pintype "bidirectional"))
    )
    (net (code "118") (name "unconnected-(U1-PJ2(XCK3{slash}PCINT11)-Pad65)") (class "Default")
      (node (ref "U1") (pin "65") (pinfunction "PJ2(XCK3/PCINT11)_65") (pintype "bidirectional"))
    )
    (net (code "119") (name "unconnected-(U1-PJ3(PCINT12)-Pad66)") (class "Default")
      (node (ref "U1") (pin "66") (pinfunction "PJ3(PCINT12)_66") (pintype "bidirectional"))
    )
    (net (code "120") (name "unconnected-(U1-PJ4(PCINT13)-Pad67)") (class "Default")
      (node (ref "U1") (pin "67") (pinfunction "PJ4(PCINT13)_67") (pintype "bidirectional"))
    )
    (net (code "121") (name "unconnected-(U1-PJ5(PCINT14)-Pad68)") (class "Default")
      (node (ref "U1") (pin "68") (pinfunction "PJ5(PCINT14)_68") (pintype "bidirectional"))
    )
    (net (code "122") (name "unconnected-(U1-PJ6(PCINT15)-Pad69)") (class "Default")
      (node (ref "U1") (pin "69") (pinfunction "PJ6(PCINT15)_69") (pintype "bidirectional"))
    )
    (net (code "123") (name "unconnected-(U1-PJ7-Pad79)") (class "Default")
      (node (ref "U1") (pin "79") (pinfunction "PJ7_79") (pintype "bidirectional"))
    )
  )
)
